# zap-1V5.net
KiCad netlist of a schematic drawn in EAGLE
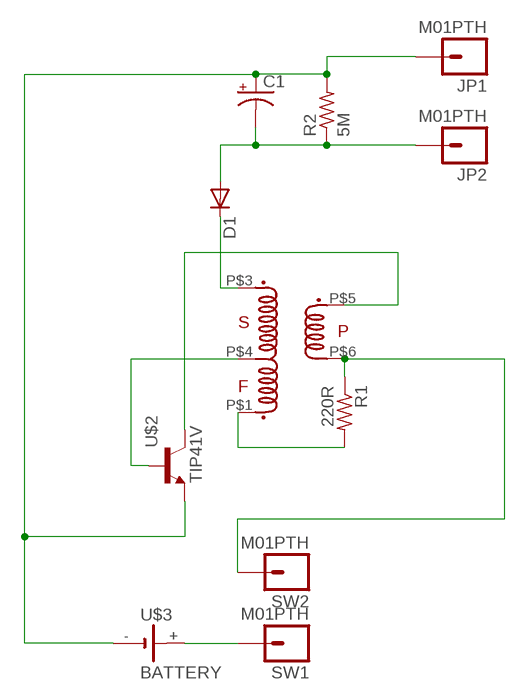
[diagram p0: schematic, sheet 1]

(export (version "E")
  (design (tool "Eeschema 10.0.6"))
  (components
    (comp (ref "C1")
      (value "CAPACITOR_POL")
      (footprint "eagle-import:E5-10,5-SIDE")
      (libsource (lib "eagle-import") (part "CAPACITOR_POL"))
    )
    (comp (ref "D1")
      (value "DIODEPTH")
      (footprint "eagle-import:DIODE-1N4001")
      (libsource (lib "eagle-import") (part "DIODEPTH"))
    )
    (comp (ref "JP1")
      (value "M01PTH")
      (footprint "eagle-import:1X01")
      (libsource (lib "eagle-import") (part "M01PTH"))
    )
    (comp (ref "JP2")
      (value "M01PTH")
      (footprint "eagle-import:1X01")
      (libsource (lib "eagle-import") (part "M01PTH"))
    )
    (comp (ref "R1")
      (value "220R")
      (footprint "eagle-import:0207_2V")
      (libsource (lib "eagle-import") (part "RESISTOR0207/2V"))
    )
    (comp (ref "R2")
      (value "5M")
      (footprint "eagle-import:0207_7")
      (libsource (lib "eagle-import") (part "RESISTOR0207/7"))
    )
    (comp (ref "SW1")
      (value "M01PTH")
      (footprint "eagle-import:1X01")
      (libsource (lib "eagle-import") (part "M01PTH"))
    )
    (comp (ref "SW2")
      (value "M01PTH")
      (footprint "eagle-import:1X01")
      (libsource (lib "eagle-import") (part "M01PTH"))
    )
    (comp (ref "U$1")
      (value "XFT-FLYBACK3V")
      (footprint "eagle-import:XFT-FLYBACK")
      (libsource (lib "eagle-import") (part "XFT-FLYBACK3V"))
    )
    (comp (ref "U$2")
      (value "TIP41V")
      (footprint "eagle-import:TO220V")
      (libsource (lib "eagle-import") (part "TIP41V"))
    )
    (comp (ref "U$3")
      (value "BATTERY")
      (footprint "eagle-import:A90")
      (libsource (lib "eagle-import") (part "BATTERY"))
    )
  )
  (nets
    (net (code "1") (name "Net-(C1-+)") (class "Default")
      (node (ref "C1") (pin "P$1") (pinfunction "+_P$1") (pintype "passive"))
      (node (ref "JP1") (pin "1") (pinfunction "1_1") (pintype "passive"))
      (node (ref "R2") (pin "2") (pinfunction "2_2") (pintype "passive"))
      (node (ref "U$2") (pin "3") (pinfunction "E_3") (pintype "passive"))
      (node (ref "U$3") (pin "-") (pinfunction "-_-") (pintype "passive"))
    )
    (net (code "2") (name "Net-(C1--)") (class "Default")
      (node (ref "C1") (pin "P$2") (pinfunction "-_P$2") (pintype "passive"))
      (node (ref "D1") (pin "A") (pinfunction "A_A") (pintype "passive"))
      (node (ref "JP2") (pin "1") (pinfunction "1_1") (pintype "passive"))
      (node (ref "R2") (pin "1") (pinfunction "1_1") (pintype "passive"))
    )
    (net (code "3") (name "Net-(SW1-Pad1)") (class "Default")
      (node (ref "SW1") (pin "1") (pinfunction "1_1") (pintype "passive"))
      (node (ref "U$3") (pin "+") (pinfunction "+_+") (pintype "passive"))
    )
    (net (code "4") (name "Net-(U$1-P$1.S)") (class "Default")
      (node (ref "D1") (pin "C") (pinfunction "C_C") (pintype "passive"))
      (node (ref "U$1") (pin "P$3") (pinfunction "P$1.S_P$3") (pintype "passive"))
    )
    (net (code "5") (name "Net-(U$1-P$2.CENTRE)") (class "Default")
      (node (ref "U$1") (pin "P$4") (pinfunction "P$2.CENTRE_P$4") (pintype "passive"))
      (node (ref "U$2") (pin "1") (pinfunction "B_1") (pintype "passive"))
    )
    (net (code "6") (name "Net-(U$1-P$3.F)") (class "Default")
      (node (ref "R1") (pin "2") (pinfunction "2_2") (pintype "passive"))
      (node (ref "U$1") (pin "P$1") (pinfunction "P$3.F_P$1") (pintype "passive"))
    )
    (net (code "7") (name "Net-(U$1-P$4.P1)") (class "Default")
      (node (ref "U$1") (pin "P$5") (pinfunction "P$4.P1_P$5") (pintype "passive"))
      (node (ref "U$2") (pin "2") (pinfunction "C_2") (pintype "passive"))
    )
    (net (code "8") (name "Net-(U$1-P$5.P2)") (class "Default")
      (node (ref "R1") (pin "1") (pinfunction "1_1") (pintype "passive"))
      (node (ref "SW2") (pin "1") (pinfunction "1_1") (pintype "passive"))
      (node (ref "U$1") (pin "P$6") (pinfunction "P$5.P2_P$6") (pintype "passive"))
    )
  )
)
